# A7_MGT_-.net
KiCad netlist of a schematic drawn in Altium Designer
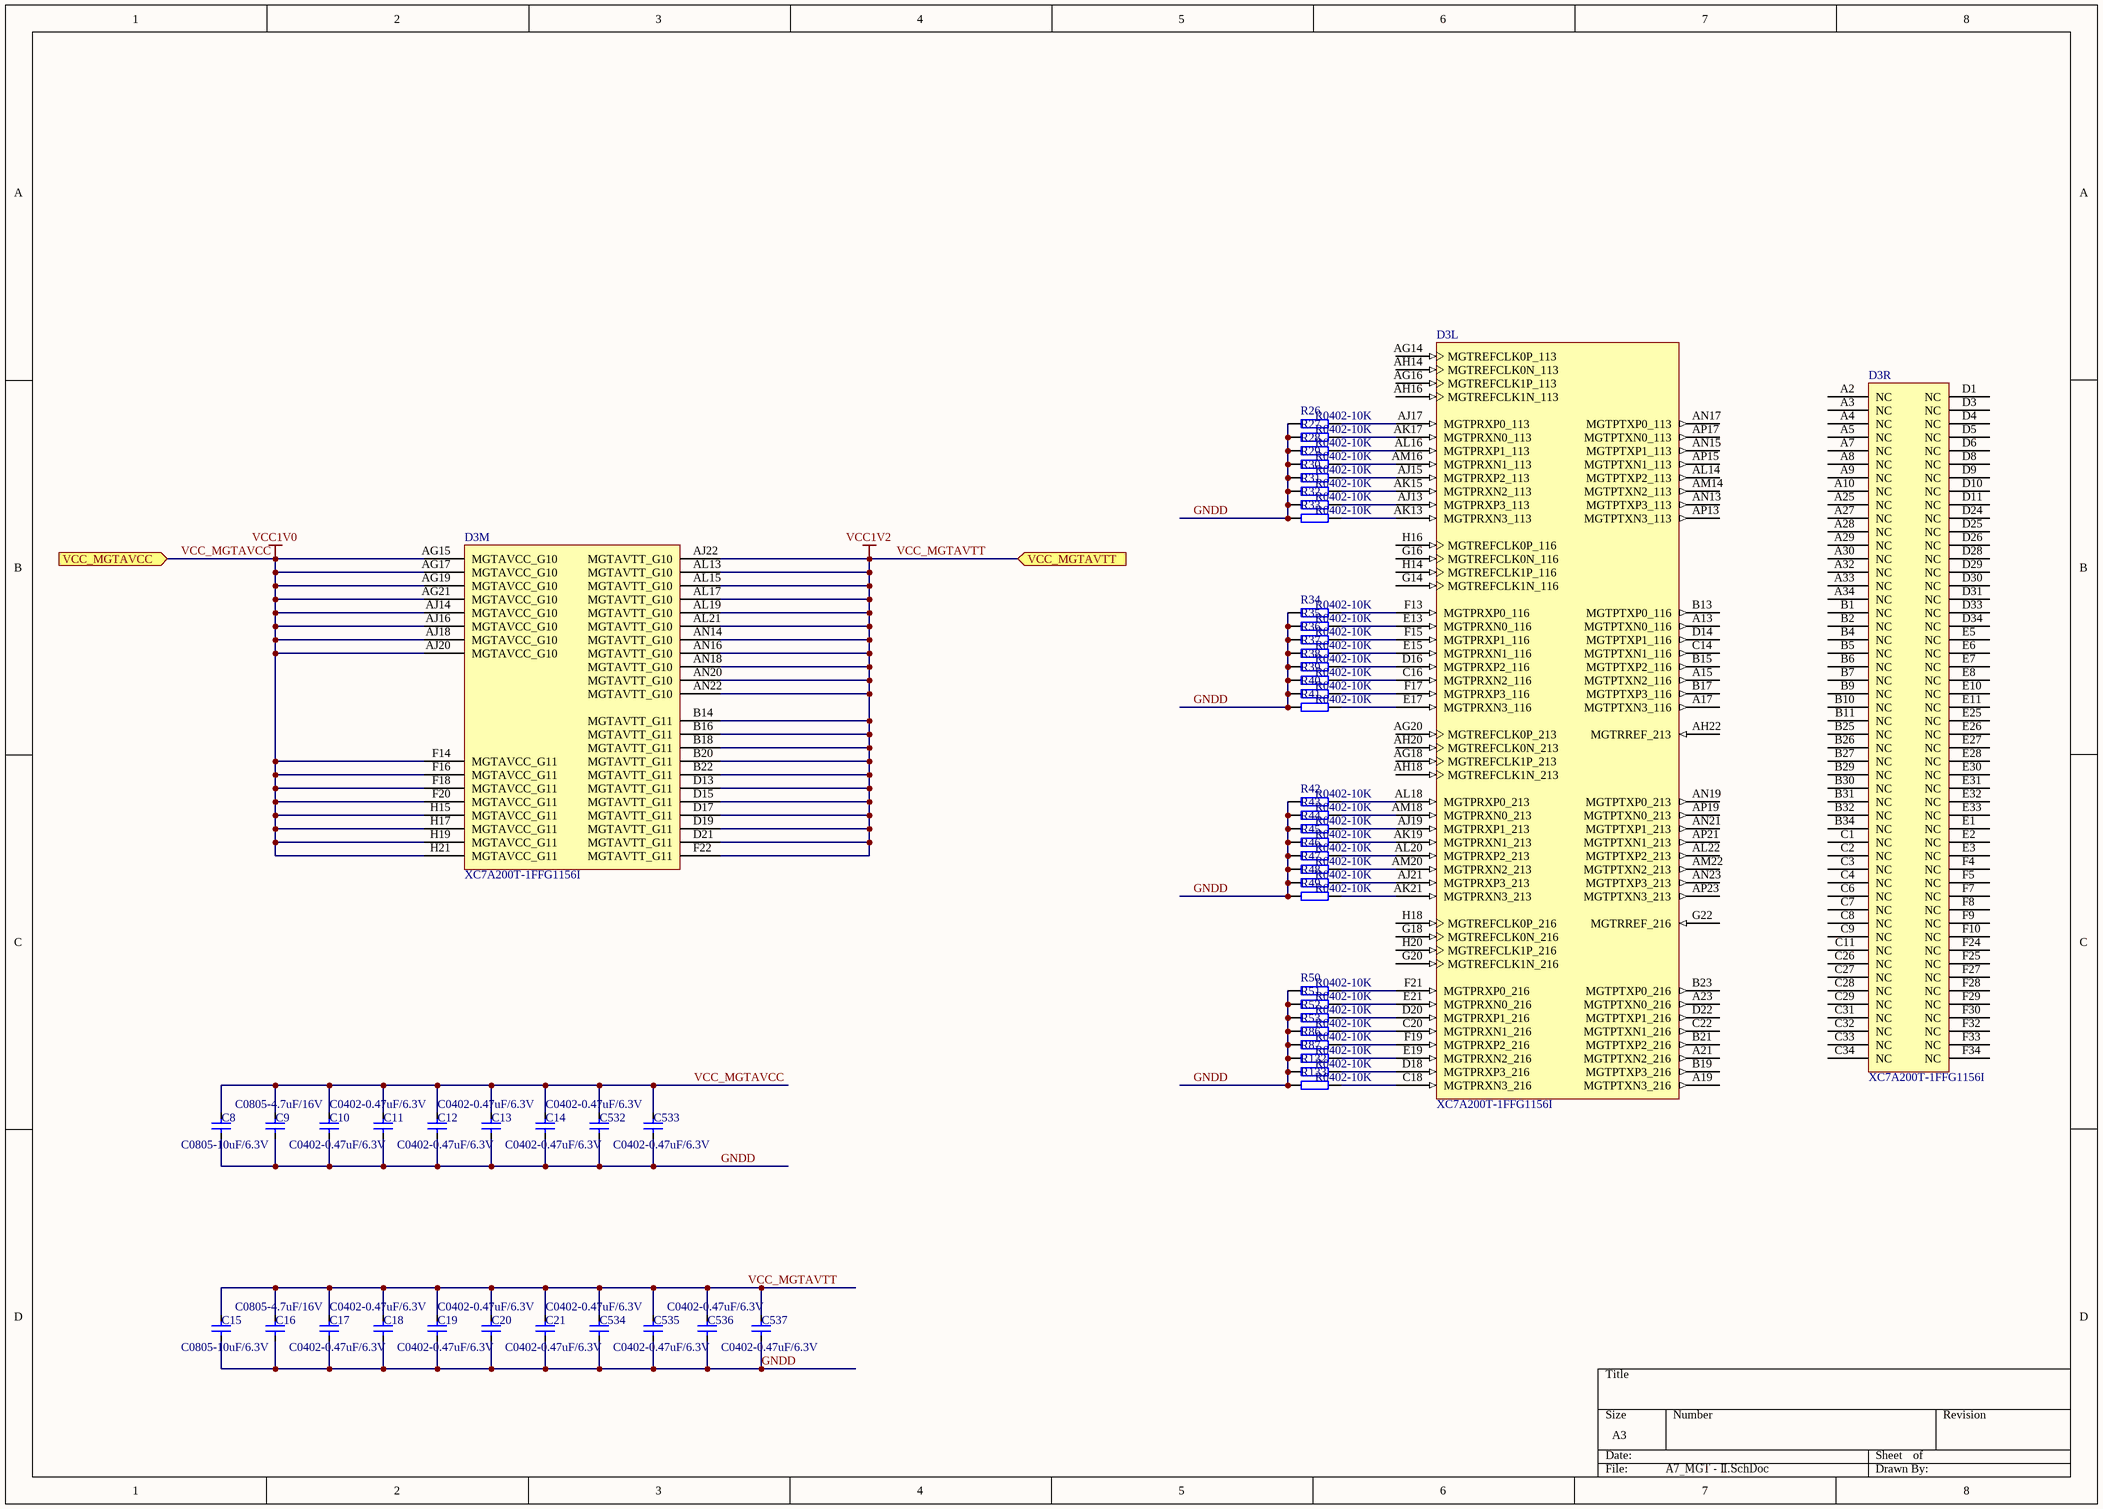
[diagram p0: A7_MGT - Ⅱ.SchDoc]

(export (version "E")
  (design (tool "Eeschema 10.0.6"))
  (components
    (comp (ref "C8")
      (value "C0805-10uF/6.3V")
      (footprint "C0805")
      (fields (field (name "SCHEMATIC_PART") "CAP"))
      (libsource (lib "Database_Libs1") (part "CAP"))
    )
    (comp (ref "C9")
      (value "C0805-4.7uF/16V")
      (footprint "C0805")
      (description "X7R")
      (fields (field (name "SCHEMATIC_PART") "CAP") (field (name "MANUFACTURER") "SAMSUNG"))
      (libsource (lib "Database_Libs1") (part "CAP"))
    )
    (comp (ref "C10")
      (value "C0402-0.47uF/6.3V")
      (footprint "C0402")
      (description "X7R")
      (fields (field (name "SCHEMATIC_PART") "CAP") (field (name "MANUFACTURER") "SAMSUNG"))
      (libsource (lib "Database_Libs1") (part "CAP"))
    )
    (comp (ref "C11")
      (value "C0402-0.47uF/6.3V")
      (footprint "C0402")
      (description "X7R")
      (fields (field (name "SCHEMATIC_PART") "CAP") (field (name "MANUFACTURER") "SAMSUNG"))
      (libsource (lib "Database_Libs1") (part "CAP"))
    )
    (comp (ref "C12")
      (value "C0402-0.47uF/6.3V")
      (footprint "C0402")
      (description "X7R")
      (fields (field (name "SCHEMATIC_PART") "CAP") (field (name "MANUFACTURER") "SAMSUNG"))
      (libsource (lib "Database_Libs1") (part "CAP"))
    )
    (comp (ref "C13")
      (value "C0402-0.47uF/6.3V")
      (footprint "C0402")
      (description "X7R")
      (fields (field (name "SCHEMATIC_PART") "CAP") (field (name "MANUFACTURER") "SAMSUNG"))
      (libsource (lib "Database_Libs1") (part "CAP"))
    )
    (comp (ref "C14")
      (value "C0402-0.47uF/6.3V")
      (footprint "C0402")
      (description "X7R")
      (fields (field (name "SCHEMATIC_PART") "CAP") (field (name "MANUFACTURER") "SAMSUNG"))
      (libsource (lib "Database_Libs1") (part "CAP"))
    )
    (comp (ref "C15")
      (value "C0805-10uF/6.3V")
      (footprint "C0805")
      (fields (field (name "SCHEMATIC_PART") "CAP"))
      (libsource (lib "Database_Libs1") (part "CAP"))
    )
    (comp (ref "C16")
      (value "C0805-4.7uF/16V")
      (footprint "C0805")
      (description "X7R")
      (fields (field (name "SCHEMATIC_PART") "CAP") (field (name "MANUFACTURER") "SAMSUNG"))
      (libsource (lib "Database_Libs1") (part "CAP"))
    )
    (comp (ref "C17")
      (value "C0402-0.47uF/6.3V")
      (footprint "C0402")
      (description "X7R")
      (fields (field (name "SCHEMATIC_PART") "CAP") (field (name "MANUFACTURER") "SAMSUNG"))
      (libsource (lib "Database_Libs1") (part "CAP"))
    )
    (comp (ref "C18")
      (value "C0402-0.47uF/6.3V")
      (footprint "C0402")
      (description "X7R")
      (fields (field (name "SCHEMATIC_PART") "CAP") (field (name "MANUFACTURER") "SAMSUNG"))
      (libsource (lib "Database_Libs1") (part "CAP"))
    )
    (comp (ref "C19")
      (value "C0402-0.47uF/6.3V")
      (footprint "C0402")
      (description "X7R")
      (fields (field (name "SCHEMATIC_PART") "CAP") (field (name "MANUFACTURER") "SAMSUNG"))
      (libsource (lib "Database_Libs1") (part "CAP"))
    )
    (comp (ref "C20")
      (value "C0402-0.47uF/6.3V")
      (footprint "C0402")
      (description "X7R")
      (fields (field (name "SCHEMATIC_PART") "CAP") (field (name "MANUFACTURER") "SAMSUNG"))
      (libsource (lib "Database_Libs1") (part "CAP"))
    )
    (comp (ref "C21")
      (value "C0402-0.47uF/6.3V")
      (footprint "C0402")
      (description "X7R")
      (fields (field (name "SCHEMATIC_PART") "CAP") (field (name "MANUFACTURER") "SAMSUNG"))
      (libsource (lib "Database_Libs1") (part "CAP"))
    )
    (comp (ref "C532")
      (value "C0402-0.47uF/6.3V")
      (footprint "C0402")
      (description "X7R")
      (fields (field (name "SCHEMATIC_PART") "CAP") (field (name "MANUFACTURER") "SAMSUNG"))
      (libsource (lib "Database_Libs1") (part "CAP"))
    )
    (comp (ref "C533")
      (value "C0402-0.47uF/6.3V")
      (footprint "C0402")
      (description "X7R")
      (fields (field (name "SCHEMATIC_PART") "CAP") (field (name "MANUFACTURER") "SAMSUNG"))
      (libsource (lib "Database_Libs1") (part "CAP"))
    )
    (comp (ref "C534")
      (value "C0402-0.47uF/6.3V")
      (footprint "C0402")
      (description "X7R")
      (fields (field (name "SCHEMATIC_PART") "CAP") (field (name "MANUFACTURER") "SAMSUNG"))
      (libsource (lib "Database_Libs1") (part "CAP"))
    )
    (comp (ref "C535")
      (value "C0402-0.47uF/6.3V")
      (footprint "C0402")
      (description "X7R")
      (fields (field (name "SCHEMATIC_PART") "CAP") (field (name "MANUFACTURER") "SAMSUNG"))
      (libsource (lib "Database_Libs1") (part "CAP"))
    )
    (comp (ref "C536")
      (value "C0402-0.47uF/6.3V")
      (footprint "C0402")
      (description "X7R")
      (fields (field (name "SCHEMATIC_PART") "CAP") (field (name "MANUFACTURER") "SAMSUNG"))
      (libsource (lib "Database_Libs1") (part "CAP"))
    )
    (comp (ref "C537")
      (value "C0402-0.47uF/6.3V")
      (footprint "C0402")
      (description "X7R")
      (fields (field (name "SCHEMATIC_PART") "CAP") (field (name "MANUFACTURER") "SAMSUNG"))
      (libsource (lib "Database_Libs1") (part "CAP"))
    )
    (comp (ref "D3")
      (value "XC7A200T-1FFG1156I")
      (footprint "FFG1156")
      (description "Artix-7 FPGA, 500 User I/Os, 16 GTP, 1156-Ball BGA, Speed Grade 1, Industrial Grade, Pb-Free")
      (fields (field (name "GENERIC PART NUMBER") "XC7A200T") (field (name "MANUFACTURER") "Xilinx"))
      (libsource (lib "Xilinx Artix-7") (part "XC7A200T-1FFG1156I"))
    )
    (comp (ref "R26")
      (value "R0402-10K")
      (footprint "R0402")
      (fields (field (name "SCHEMATIC_PART") "RES") (field (name "MANUFACTURER") "SAMSUNG"))
      (libsource (lib "Database_Libs1") (part "RES"))
    )
    (comp (ref "R27")
      (value "R0402-10K")
      (footprint "R0402")
      (fields (field (name "SCHEMATIC_PART") "RES") (field (name "MANUFACTURER") "SAMSUNG"))
      (libsource (lib "Database_Libs1") (part "RES"))
    )
    (comp (ref "R28")
      (value "R0402-10K")
      (footprint "R0402")
      (fields (field (name "SCHEMATIC_PART") "RES") (field (name "MANUFACTURER") "SAMSUNG"))
      (libsource (lib "Database_Libs1") (part "RES"))
    )
    (comp (ref "R29")
      (value "R0402-10K")
      (footprint "R0402")
      (fields (field (name "SCHEMATIC_PART") "RES") (field (name "MANUFACTURER") "SAMSUNG"))
      (libsource (lib "Database_Libs1") (part "RES"))
    )
    (comp (ref "R30")
      (value "R0402-10K")
      (footprint "R0402")
      (fields (field (name "SCHEMATIC_PART") "RES") (field (name "MANUFACTURER") "SAMSUNG"))
      (libsource (lib "Database_Libs1") (part "RES"))
    )
    (comp (ref "R31")
      (value "R0402-10K")
      (footprint "R0402")
      (fields (field (name "SCHEMATIC_PART") "RES") (field (name "MANUFACTURER") "SAMSUNG"))
      (libsource (lib "Database_Libs1") (part "RES"))
    )
    (comp (ref "R32")
      (value "R0402-10K")
      (footprint "R0402")
      (fields (field (name "SCHEMATIC_PART") "RES") (field (name "MANUFACTURER") "SAMSUNG"))
      (libsource (lib "Database_Libs1") (part "RES"))
    )
    (comp (ref "R33")
      (value "R0402-10K")
      (footprint "R0402")
      (fields (field (name "SCHEMATIC_PART") "RES") (field (name "MANUFACTURER") "SAMSUNG"))
      (libsource (lib "Database_Libs1") (part "RES"))
    )
    (comp (ref "R34")
      (value "R0402-10K")
      (footprint "R0402")
      (fields (field (name "SCHEMATIC_PART") "RES") (field (name "MANUFACTURER") "SAMSUNG"))
      (libsource (lib "Database_Libs1") (part "RES"))
    )
    (comp (ref "R35")
      (value "R0402-10K")
      (footprint "R0402")
      (fields (field (name "SCHEMATIC_PART") "RES") (field (name "MANUFACTURER") "SAMSUNG"))
      (libsource (lib "Database_Libs1") (part "RES"))
    )
    (comp (ref "R36")
      (value "R0402-10K")
      (footprint "R0402")
      (fields (field (name "SCHEMATIC_PART") "RES") (field (name "MANUFACTURER") "SAMSUNG"))
      (libsource (lib "Database_Libs1") (part "RES"))
    )
    (comp (ref "R37")
      (value "R0402-10K")
      (footprint "R0402")
      (fields (field (name "SCHEMATIC_PART") "RES") (field (name "MANUFACTURER") "SAMSUNG"))
      (libsource (lib "Database_Libs1") (part "RES"))
    )
    (comp (ref "R38")
      (value "R0402-10K")
      (footprint "R0402")
      (fields (field (name "SCHEMATIC_PART") "RES") (field (name "MANUFACTURER") "SAMSUNG"))
      (libsource (lib "Database_Libs1") (part "RES"))
    )
    (comp (ref "R39")
      (value "R0402-10K")
      (footprint "R0402")
      (fields (field (name "SCHEMATIC_PART") "RES") (field (name "MANUFACTURER") "SAMSUNG"))
      (libsource (lib "Database_Libs1") (part "RES"))
    )
    (comp (ref "R40")
      (value "R0402-10K")
      (footprint "R0402")
      (fields (field (name "SCHEMATIC_PART") "RES") (field (name "MANUFACTURER") "SAMSUNG"))
      (libsource (lib "Database_Libs1") (part "RES"))
    )
    (comp (ref "R41")
      (value "R0402-10K")
      (footprint "R0402")
      (fields (field (name "SCHEMATIC_PART") "RES") (field (name "MANUFACTURER") "SAMSUNG"))
      (libsource (lib "Database_Libs1") (part "RES"))
    )
    (comp (ref "R42")
      (value "R0402-10K")
      (footprint "R0402")
      (fields (field (name "SCHEMATIC_PART") "RES") (field (name "MANUFACTURER") "SAMSUNG"))
      (libsource (lib "Database_Libs1") (part "RES"))
    )
    (comp (ref "R43")
      (value "R0402-10K")
      (footprint "R0402")
      (fields (field (name "SCHEMATIC_PART") "RES") (field (name "MANUFACTURER") "SAMSUNG"))
      (libsource (lib "Database_Libs1") (part "RES"))
    )
    (comp (ref "R44")
      (value "R0402-10K")
      (footprint "R0402")
      (fields (field (name "SCHEMATIC_PART") "RES") (field (name "MANUFACTURER") "SAMSUNG"))
      (libsource (lib "Database_Libs1") (part "RES"))
    )
    (comp (ref "R45")
      (value "R0402-10K")
      (footprint "R0402")
      (fields (field (name "SCHEMATIC_PART") "RES") (field (name "MANUFACTURER") "SAMSUNG"))
      (libsource (lib "Database_Libs1") (part "RES"))
    )
    (comp (ref "R46")
      (value "R0402-10K")
      (footprint "R0402")
      (fields (field (name "SCHEMATIC_PART") "RES") (field (name "MANUFACTURER") "SAMSUNG"))
      (libsource (lib "Database_Libs1") (part "RES"))
    )
    (comp (ref "R47")
      (value "R0402-10K")
      (footprint "R0402")
      (fields (field (name "SCHEMATIC_PART") "RES") (field (name "MANUFACTURER") "SAMSUNG"))
      (libsource (lib "Database_Libs1") (part "RES"))
    )
    (comp (ref "R48")
      (value "R0402-10K")
      (footprint "R0402")
      (fields (field (name "SCHEMATIC_PART") "RES") (field (name "MANUFACTURER") "SAMSUNG"))
      (libsource (lib "Database_Libs1") (part "RES"))
    )
    (comp (ref "R49")
      (value "R0402-10K")
      (footprint "R0402")
      (fields (field (name "SCHEMATIC_PART") "RES") (field (name "MANUFACTURER") "SAMSUNG"))
      (libsource (lib "Database_Libs1") (part "RES"))
    )
    (comp (ref "R50")
      (value "R0402-10K")
      (footprint "R0402")
      (fields (field (name "SCHEMATIC_PART") "RES") (field (name "MANUFACTURER") "SAMSUNG"))
      (libsource (lib "Database_Libs1") (part "RES"))
    )
    (comp (ref "R51")
      (value "R0402-10K")
      (footprint "R0402")
      (fields (field (name "SCHEMATIC_PART") "RES") (field (name "MANUFACTURER") "SAMSUNG"))
      (libsource (lib "Database_Libs1") (part "RES"))
    )
    (comp (ref "R52")
      (value "R0402-10K")
      (footprint "R0402")
      (fields (field (name "SCHEMATIC_PART") "RES") (field (name "MANUFACTURER") "SAMSUNG"))
      (libsource (lib "Database_Libs1") (part "RES"))
    )
    (comp (ref "R53")
      (value "R0402-10K")
      (footprint "R0402")
      (fields (field (name "SCHEMATIC_PART") "RES") (field (name "MANUFACTURER") "SAMSUNG"))
      (libsource (lib "Database_Libs1") (part "RES"))
    )
    (comp (ref "R86")
      (value "R0402-10K")
      (footprint "R0402")
      (fields (field (name "SCHEMATIC_PART") "RES") (field (name "MANUFACTURER") "SAMSUNG"))
      (libsource (lib "Database_Libs1") (part "RES"))
    )
    (comp (ref "R87")
      (value "R0402-10K")
      (footprint "R0402")
      (fields (field (name "SCHEMATIC_PART") "RES") (field (name "MANUFACTURER") "SAMSUNG"))
      (libsource (lib "Database_Libs1") (part "RES"))
    )
    (comp (ref "R132")
      (value "R0402-10K")
      (footprint "R0402")
      (fields (field (name "SCHEMATIC_PART") "RES") (field (name "MANUFACTURER") "SAMSUNG"))
      (libsource (lib "Database_Libs1") (part "RES"))
    )
    (comp (ref "R133")
      (value "R0402-10K")
      (footprint "R0402")
      (fields (field (name "SCHEMATIC_PART") "RES") (field (name "MANUFACTURER") "SAMSUNG"))
      (libsource (lib "Database_Libs1") (part "RES"))
    )
  )
  (nets
    (net (code "1") (name "/GNDD") (class "Default")
      (node (ref "C10") (pin "2") (pinfunction "2_2") (pintype "passive"))
      (node (ref "C11") (pin "2") (pinfunction "2_2") (pintype "passive"))
      (node (ref "C12") (pin "2") (pinfunction "2_2") (pintype "passive"))
      (node (ref "C13") (pin "2") (pinfunction "2_2") (pintype "passive"))
      (node (ref "C14") (pin "2") (pinfunction "2_2") (pintype "passive"))
      (node (ref "C15") (pin "2") (pinfunction "2_2") (pintype "passive"))
      (node (ref "C16") (pin "2") (pinfunction "2_2") (pintype "passive"))
      (node (ref "C17") (pin "2") (pinfunction "2_2") (pintype "passive"))
      (node (ref "C18") (pin "2") (pinfunction "2_2") (pintype "passive"))
      (node (ref "C19") (pin "2") (pinfunction "2_2") (pintype "passive"))
      (node (ref "C20") (pin "2") (pinfunction "2_2") (pintype "passive"))
      (node (ref "C21") (pin "2") (pinfunction "2_2") (pintype "passive"))
      (node (ref "C532") (pin "2") (pinfunction "2_2") (pintype "passive"))
      (node (ref "C533") (pin "2") (pinfunction "2_2") (pintype "passive"))
      (node (ref "C534") (pin "2") (pinfunction "2_2") (pintype "passive"))
      (node (ref "C535") (pin "2") (pinfunction "2_2") (pintype "passive"))
      (node (ref "C536") (pin "2") (pinfunction "2_2") (pintype "passive"))
      (node (ref "C537") (pin "2") (pinfunction "2_2") (pintype "passive"))
      (node (ref "C8") (pin "2") (pinfunction "2_2") (pintype "passive"))
      (node (ref "C9") (pin "2") (pinfunction "2_2") (pintype "passive"))
      (node (ref "R132") (pin "1") (pintype "passive"))
      (node (ref "R133") (pin "1") (pintype "passive"))
      (node (ref "R26") (pin "1") (pintype "passive"))
      (node (ref "R27") (pin "1") (pintype "passive"))
      (node (ref "R28") (pin "1") (pintype "passive"))
      (node (ref "R29") (pin "1") (pintype "passive"))
      (node (ref "R30") (pin "1") (pintype "passive"))
      (node (ref "R31") (pin "1") (pintype "passive"))
      (node (ref "R32") (pin "1") (pintype "passive"))
      (node (ref "R33") (pin "1") (pintype "passive"))
      (node (ref "R34") (pin "1") (pintype "passive"))
      (node (ref "R35") (pin "1") (pintype "passive"))
      (node (ref "R36") (pin "1") (pintype "passive"))
      (node (ref "R37") (pin "1") (pintype "passive"))
      (node (ref "R38") (pin "1") (pintype "passive"))
      (node (ref "R39") (pin "1") (pintype "passive"))
      (node (ref "R40") (pin "1") (pintype "passive"))
      (node (ref "R41") (pin "1") (pintype "passive"))
      (node (ref "R42") (pin "1") (pintype "passive"))
      (node (ref "R43") (pin "1") (pintype "passive"))
      (node (ref "R44") (pin "1") (pintype "passive"))
      (node (ref "R45") (pin "1") (pintype "passive"))
      (node (ref "R46") (pin "1") (pintype "passive"))
      (node (ref "R47") (pin "1") (pintype "passive"))
      (node (ref "R48") (pin "1") (pintype "passive"))
      (node (ref "R49") (pin "1") (pintype "passive"))
      (node (ref "R50") (pin "1") (pintype "passive"))
      (node (ref "R51") (pin "1") (pintype "passive"))
      (node (ref "R52") (pin "1") (pintype "passive"))
      (node (ref "R53") (pin "1") (pintype "passive"))
      (node (ref "R86") (pin "1") (pintype "passive"))
      (node (ref "R87") (pin "1") (pintype "passive"))
    )
    (net (code "2") (name "Net-(D3L-MGTPRXN0_113)") (class "Default")
      (node (ref "D3") (pin "AK17") (pinfunction "MGTPRXN0_113_AK17") (pintype "input"))
      (node (ref "R27") (pin "2") (pintype "passive"))
    )
    (net (code "3") (name "Net-(D3L-MGTPRXN0_116)") (class "Default")
      (node (ref "D3") (pin "E13") (pinfunction "MGTPRXN0_116_E13") (pintype "input"))
      (node (ref "R35") (pin "2") (pintype "passive"))
    )
    (net (code "4") (name "Net-(D3L-MGTPRXN0_213)") (class "Default")
      (node (ref "D3") (pin "AM18") (pinfunction "MGTPRXN0_213_AM18") (pintype "input"))
      (node (ref "R43") (pin "2") (pintype "passive"))
    )
    (net (code "5") (name "Net-(D3L-MGTPRXN0_216)") (class "Default")
      (node (ref "D3") (pin "E21") (pinfunction "MGTPRXN0_216_E21") (pintype "input"))
      (node (ref "R51") (pin "2") (pintype "passive"))
    )
    (net (code "6") (name "Net-(D3L-MGTPRXN1_113)") (class "Default")
      (node (ref "D3") (pin "AM16") (pinfunction "MGTPRXN1_113_AM16") (pintype "input"))
      (node (ref "R29") (pin "2") (pintype "passive"))
    )
    (net (code "7") (name "Net-(D3L-MGTPRXN1_116)") (class "Default")
      (node (ref "D3") (pin "E15") (pinfunction "MGTPRXN1_116_E15") (pintype "input"))
      (node (ref "R37") (pin "2") (pintype "passive"))
    )
    (net (code "8") (name "Net-(D3L-MGTPRXN1_213)") (class "Default")
      (node (ref "D3") (pin "AK19") (pinfunction "MGTPRXN1_213_AK19") (pintype "input"))
      (node (ref "R45") (pin "2") (pintype "passive"))
    )
    (net (code "9") (name "Net-(D3L-MGTPRXN1_216)") (class "Default")
      (node (ref "D3") (pin "C20") (pinfunction "MGTPRXN1_216_C20") (pintype "input"))
      (node (ref "R53") (pin "2") (pintype "passive"))
    )
    (net (code "10") (name "Net-(D3L-MGTPRXN2_113)") (class "Default")
      (node (ref "D3") (pin "AK15") (pinfunction "MGTPRXN2_113_AK15") (pintype "input"))
      (node (ref "R31") (pin "2") (pintype "passive"))
    )
    (net (code "11") (name "Net-(D3L-MGTPRXN2_116)") (class "Default")
      (node (ref "D3") (pin "C16") (pinfunction "MGTPRXN2_116_C16") (pintype "input"))
      (node (ref "R39") (pin "2") (pintype "passive"))
    )
    (net (code "12") (name "Net-(D3L-MGTPRXN2_213)") (class "Default")
      (node (ref "D3") (pin "AM20") (pinfunction "MGTPRXN2_213_AM20") (pintype "input"))
      (node (ref "R47") (pin "2") (pintype "passive"))
    )
    (net (code "13") (name "Net-(D3L-MGTPRXN2_216)") (class "Default")
      (node (ref "D3") (pin "E19") (pinfunction "MGTPRXN2_216_E19") (pintype "input"))
      (node (ref "R87") (pin "2") (pintype "passive"))
    )
    (net (code "14") (name "Net-(D3L-MGTPRXN3_113)") (class "Default")
      (node (ref "D3") (pin "AK13") (pinfunction "MGTPRXN3_113_AK13") (pintype "input"))
      (node (ref "R33") (pin "2") (pintype "passive"))
    )
    (net (code "15") (name "Net-(D3L-MGTPRXN3_116)") (class "Default")
      (node (ref "D3") (pin "E17") (pinfunction "MGTPRXN3_116_E17") (pintype "input"))
      (node (ref "R41") (pin "2") (pintype "passive"))
    )
    (net (code "16") (name "Net-(D3L-MGTPRXN3_213)") (class "Default")
      (node (ref "D3") (pin "AK21") (pinfunction "MGTPRXN3_213_AK21") (pintype "input"))
      (node (ref "R49") (pin "2") (pintype "passive"))
    )
    (net (code "17") (name "Net-(D3L-MGTPRXN3_216)") (class "Default")
      (node (ref "D3") (pin "C18") (pinfunction "MGTPRXN3_216_C18") (pintype "input"))
      (node (ref "R133") (pin "2") (pintype "passive"))
    )
    (net (code "18") (name "Net-(D3L-MGTPRXP0_113)") (class "Default")
      (node (ref "D3") (pin "AJ17") (pinfunction "MGTPRXP0_113_AJ17") (pintype "input"))
      (node (ref "R26") (pin "2") (pintype "passive"))
    )
    (net (code "19") (name "Net-(D3L-MGTPRXP0_116)") (class "Default")
      (node (ref "D3") (pin "F13") (pinfunction "MGTPRXP0_116_F13") (pintype "input"))
      (node (ref "R34") (pin "2") (pintype "passive"))
    )
    (net (code "20") (name "Net-(D3L-MGTPRXP0_213)") (class "Default")
      (node (ref "D3") (pin "AL18") (pinfunction "MGTPRXP0_213_AL18") (pintype "input"))
      (node (ref "R42") (pin "2") (pintype "passive"))
    )
    (net (code "21") (name "Net-(D3L-MGTPRXP0_216)") (class "Default")
      (node (ref "D3") (pin "F21") (pinfunction "MGTPRXP0_216_F21") (pintype "input"))
      (node (ref "R50") (pin "2") (pintype "passive"))
    )
    (net (code "22") (name "Net-(D3L-MGTPRXP1_113)") (class "Default")
      (node (ref "D3") (pin "AL16") (pinfunction "MGTPRXP1_113_AL16") (pintype "input"))
      (node (ref "R28") (pin "2") (pintype "passive"))
    )
    (net (code "23") (name "Net-(D3L-MGTPRXP1_116)") (class "Default")
      (node (ref "D3") (pin "F15") (pinfunction "MGTPRXP1_116_F15") (pintype "input"))
      (node (ref "R36") (pin "2") (pintype "passive"))
    )
    (net (code "24") (name "Net-(D3L-MGTPRXP1_213)") (class "Default")
      (node (ref "D3") (pin "AJ19") (pinfunction "MGTPRXP1_213_AJ19") (pintype "input"))
      (node (ref "R44") (pin "2") (pintype "passive"))
    )
    (net (code "25") (name "Net-(D3L-MGTPRXP1_216)") (class "Default")
      (node (ref "D3") (pin "D20") (pinfunction "MGTPRXP1_216_D20") (pintype "input"))
      (node (ref "R52") (pin "2") (pintype "passive"))
    )
    (net (code "26") (name "Net-(D3L-MGTPRXP2_113)") (class "Default")
      (node (ref "D3") (pin "AJ15") (pinfunction "MGTPRXP2_113_AJ15") (pintype "input"))
      (node (ref "R30") (pin "2") (pintype "passive"))
    )
    (net (code "27") (name "Net-(D3L-MGTPRXP2_116)") (class "Default")
      (node (ref "D3") (pin "D16") (pinfunction "MGTPRXP2_116_D16") (pintype "input"))
      (node (ref "R38") (pin "2") (pintype "passive"))
    )
    (net (code "28") (name "Net-(D3L-MGTPRXP2_213)") (class "Default")
      (node (ref "D3") (pin "AL20") (pinfunction "MGTPRXP2_213_AL20") (pintype "input"))
      (node (ref "R46") (pin "2") (pintype "passive"))
    )
    (net (code "29") (name "Net-(D3L-MGTPRXP2_216)") (class "Default")
      (node (ref "D3") (pin "F19") (pinfunction "MGTPRXP2_216_F19") (pintype "input"))
      (node (ref "R86") (pin "2") (pintype "passive"))
    )
    (net (code "30") (name "Net-(D3L-MGTPRXP3_113)") (class "Default")
      (node (ref "D3") (pin "AJ13") (pinfunction "MGTPRXP3_113_AJ13") (pintype "input"))
      (node (ref "R32") (pin "2") (pintype "passive"))
    )
    (net (code "31") (name "Net-(D3L-MGTPRXP3_116)") (class "Default")
      (node (ref "D3") (pin "F17") (pinfunction "MGTPRXP3_116_F17") (pintype "input"))
      (node (ref "R40") (pin "2") (pintype "passive"))
    )
    (net (code "32") (name "Net-(D3L-MGTPRXP3_213)") (class "Default")
      (node (ref "D3") (pin "AJ21") (pinfunction "MGTPRXP3_213_AJ21") (pintype "input"))
      (node (ref "R48") (pin "2") (pintype "passive"))
    )
    (net (code "33") (name "Net-(D3L-MGTPRXP3_216)") (class "Default")
      (node (ref "D3") (pin "D18") (pinfunction "MGTPRXP3_216_D18") (pintype "input"))
      (node (ref "R132") (pin "2") (pintype "passive"))
    )
    (net (code "34") (name "VCC1V0") (class "Default")
      (node (ref "C10") (pin "1") (pinfunction "1_1") (pintype "passive"))
      (node (ref "C11") (pin "1") (pinfunction "1_1") (pintype "passive"))
      (node (ref "C12") (pin "1") (pinfunction "1_1") (pintype "passive"))
      (node (ref "C13") (pin "1") (pinfunction "1_1") (pintype "passive"))
      (node (ref "C14") (pin "1") (pinfunction "1_1") (pintype "passive"))
      (node (ref "C532") (pin "1") (pinfunction "1_1") (pintype "passive"))
      (node (ref "C533") (pin "1") (pinfunction "1_1") (pintype "passive"))
      (node (ref "C8") (pin "1") (pinfunction "1_1") (pintype "passive"))
      (node (ref "C9") (pin "1") (pinfunction "1_1") (pintype "passive"))
      (node (ref "D3") (pin "AG15") (pinfunction "MGTAVCC_G10_AG15") (pintype "power_in"))
      (node (ref "D3") (pin "AG17") (pinfunction "MGTAVCC_G10_AG17") (pintype "power_in"))
      (node (ref "D3") (pin "AG19") (pinfunction "MGTAVCC_G10_AG19") (pintype "power_in"))
      (node (ref "D3") (pin "AG21") (pinfunction "MGTAVCC_G10_AG21") (pintype "power_in"))
      (node (ref "D3") (pin "AJ14") (pinfunction "MGTAVCC_G10_AJ14") (pintype "power_in"))
      (node (ref "D3") (pin "AJ16") (pinfunction "MGTAVCC_G10_AJ16") (pintype "power_in"))
      (node (ref "D3") (pin "AJ18") (pinfunction "MGTAVCC_G10_AJ18") (pintype "power_in"))
      (node (ref "D3") (pin "AJ20") (pinfunction "MGTAVCC_G10_AJ20") (pintype "power_in"))
      (node (ref "D3") (pin "F14") (pinfunction "MGTAVCC_G11_F14") (pintype "power_in"))
      (node (ref "D3") (pin "F16") (pinfunction "MGTAVCC_G11_F16") (pintype "power_in"))
      (node (ref "D3") (pin "F18") (pinfunction "MGTAVCC_G11_F18") (pintype "power_in"))
      (node (ref "D3") (pin "F20") (pinfunction "MGTAVCC_G11_F20") (pintype "power_in"))
      (node (ref "D3") (pin "H15") (pinfunction "MGTAVCC_G11_H15") (pintype "power_in"))
      (node (ref "D3") (pin "H17") (pinfunction "MGTAVCC_G11_H17") (pintype "power_in"))
      (node (ref "D3") (pin "H19") (pinfunction "MGTAVCC_G11_H19") (pintype "power_in"))
      (node (ref "D3") (pin "H21") (pinfunction "MGTAVCC_G11_H21") (pintype "power_in"))
    )
    (net (code "35") (name "VCC1V2") (class "Default")
      (node (ref "C15") (pin "1") (pinfunction "1_1") (pintype "passive"))
      (node (ref "C16") (pin "1") (pinfunction "1_1") (pintype "passive"))
      (node (ref "C17") (pin "1") (pinfunction "1_1") (pintype "passive"))
      (node (ref "C18") (pin "1") (pinfunction "1_1") (pintype "passive"))
      (node (ref "C19") (pin "1") (pinfunction "1_1") (pintype "passive"))
      (node (ref "C20") (pin "1") (pinfunction "1_1") (pintype "passive"))
      (node (ref "C21") (pin "1") (pinfunction "1_1") (pintype "passive"))
      (node (ref "C534") (pin "1") (pinfunction "1_1") (pintype "passive"))
      (node (ref "C535") (pin "1") (pinfunction "1_1") (pintype "passive"))
      (node (ref "C536") (pin "1") (pinfunction "1_1") (pintype "passive"))
      (node (ref "C537") (pin "1") (pinfunction "1_1") (pintype "passive"))
      (node (ref "D3") (pin "AJ22") (pinfunction "MGTAVTT_G10_AJ22") (pintype "power_in"))
      (node (ref "D3") (pin "AL13") (pinfunction "MGTAVTT_G10_AL13") (pintype "power_in"))
      (node (ref "D3") (pin "AL15") (pinfunction "MGTAVTT_G10_AL15") (pintype "power_in"))
      (node (ref "D3") (pin "AL17") (pinfunction "MGTAVTT_G10_AL17") (pintype "power_in"))
      (node (ref "D3") (pin "AL19") (pinfunction "MGTAVTT_G10_AL19") (pintype "power_in"))
      (node (ref "D3") (pin "AL21") (pinfunction "MGTAVTT_G10_AL21") (pintype "power_in"))
      (node (ref "D3") (pin "AN14") (pinfunction "MGTAVTT_G10_AN14") (pintype "power_in"))
      (node (ref "D3") (pin "AN16") (pinfunction "MGTAVTT_G10_AN16") (pintype "power_in"))
      (node (ref "D3") (pin "AN18") (pinfunction "MGTAVTT_G10_AN18") (pintype "power_in"))
      (node (ref "D3") (pin "AN20") (pinfunction "MGTAVTT_G10_AN20") (pintype "power_in"))
      (node (ref "D3") (pin "AN22") (pinfunction "MGTAVTT_G10_AN22") (pintype "power_in"))
      (node (ref "D3") (pin "B14") (pinfunction "MGTAVTT_G11_B14") (pintype "power_in"))
      (node (ref "D3") (pin "B16") (pinfunction "MGTAVTT_G11_B16") (pintype "power_in"))
      (node (ref "D3") (pin "B18") (pinfunction "MGTAVTT_G11_B18") (pintype "power_in"))
      (node (ref "D3") (pin "B20") (pinfunction "MGTAVTT_G11_B20") (pintype "power_in"))
      (node (ref "D3") (pin "B22") (pinfunction "MGTAVTT_G11_B22") (pintype "power_in"))
      (node (ref "D3") (pin "D13") (pinfunction "MGTAVTT_G11_D13") (pintype "power_in"))
      (node (ref "D3") (pin "D15") (pinfunction "MGTAVTT_G11_D15") (pintype "power_in"))
      (node (ref "D3") (pin "D17") (pinfunction "MGTAVTT_G11_D17") (pintype "power_in"))
      (node (ref "D3") (pin "D19") (pinfunction "MGTAVTT_G11_D19") (pintype "power_in"))
      (node (ref "D3") (pin "D21") (pinfunction "MGTAVTT_G11_D21") (pintype "power_in"))
      (node (ref "D3") (pin "F22") (pinfunction "MGTAVTT_G11_F22") (pintype "power_in"))
    )
    (net (code "36") (name "unconnected-(D3L-MGTPTXN0_113-PadAP17)") (class "Default")
      (node (ref "D3") (pin "AP17") (pinfunction "MGTPTXN0_113_AP17") (pintype "output"))
    )
    (net (code "37") (name "unconnected-(D3L-MGTPTXN0_116-PadA13)") (class "Default")
      (node (ref "D3") (pin "A13") (pinfunction "MGTPTXN0_116_A13") (pintype "output"))
    )
    (net (code "38") (name "unconnected-(D3L-MGTPTXN0_213-PadAP19)") (class "Default")
      (node (ref "D3") (pin "AP19") (pinfunction "MGTPTXN0_213_AP19") (pintype "output"))
    )
    (net (code "39") (name "unconnected-(D3L-MGTPTXN0_216-PadA23)") (class "Default")
      (node (ref "D3") (pin "A23") (pinfunction "MGTPTXN0_216_A23") (pintype "output"))
    )
    (net (code "40") (name "unconnected-(D3L-MGTPTXN1_113-PadAP15)") (class "Default")
      (node (ref "D3") (pin "AP15") (pinfunction "MGTPTXN1_113_AP15") (pintype "output"))
    )
    (net (code "41") (name "unconnected-(D3L-MGTPTXN1_116-PadC14)") (class "Default")
      (node (ref "D3") (pin "C14") (pinfunction "MGTPTXN1_116_C14") (pintype "output"))
    )
    (net (code "42") (name "unconnected-(D3L-MGTPTXN1_213-PadAP21)") (class "Default")
      (node (ref "D3") (pin "AP21") (pinfunction "MGTPTXN1_213_AP21") (pintype "output"))
    )
    (net (code "43") (name "unconnected-(D3L-MGTPTXN1_216-PadC22)") (class "Default")
      (node (ref "D3") (pin "C22") (pinfunction "MGTPTXN1_216_C22") (pintype "output"))
    )
    (net (code "44") (name "unconnected-(D3L-MGTPTXN2_113-PadAM14)") (class "Default")
      (node (ref "D3") (pin "AM14") (pinfunction "MGTPTXN2_113_AM14") (pintype "output"))
    )
    (net (code "45") (name "unconnected-(D3L-MGTPTXN2_116-PadA15)") (class "Default")
      (node (ref "D3") (pin "A15") (pinfunction "MGTPTXN2_116_A15") (pintype "output"))
    )
    (net (code "46") (name "unconnected-(D3L-MGTPTXN2_213-PadAM22)") (class "Default")
      (node (ref "D3") (pin "AM22") (pinfunction "MGTPTXN2_213_AM22") (pintype "output"))
    )
    (net (code "47") (name "unconnected-(D3L-MGTPTXN2_216-PadA21)") (class "Default")
      (node (ref "D3") (pin "A21") (pinfunction "MGTPTXN2_216_A21") (pintype "output"))
    )
    (net (code "48") (name "unconnected-(D3L-MGTPTXN3_113-PadAP13)") (class "Default")
      (node (ref "D3") (pin "AP13") (pinfunction "MGTPTXN3_113_AP13") (pintype "output"))
    )
    (net (code "49") (name "unconnected-(D3L-MGTPTXN3_116-PadA17)") (class "Default")
      (node (ref "D3") (pin "A17") (pinfunction "MGTPTXN3_116_A17") (pintype "output"))
    )
    (net (code "50") (name "unconnected-(D3L-MGTPTXN3_213-PadAP23)") (class "Default")
      (node (ref "D3") (pin "AP23") (pinfunction "MGTPTXN3_213_AP23") (pintype "output"))
    )
    (net (code "51") (name "unconnected-(D3L-MGTPTXN3_216-PadA19)") (class "Default")
      (node (ref "D3") (pin "A19") (pinfunction "MGTPTXN3_216_A19") (pintype "output"))
    )
    (net (code "52") (name "unconnected-(D3L-MGTPTXP0_113-PadAN17)") (class "Default")
      (node (ref "D3") (pin "AN17") (pinfunction "MGTPTXP0_113_AN17") (pintype "output"))
    )
    (net (code "53") (name "unconnected-(D3L-MGTPTXP0_116-PadB13)") (class "Default")
      (node (ref "D3") (pin "B13") (pinfunction "MGTPTXP0_116_B13") (pintype "output"))
    )
    (net (code "54") (name "unconnected-(D3L-MGTPTXP0_213-PadAN19)") (class "Default")
      (node (ref "D3") (pin "AN19") (pinfunction "MGTPTXP0_213_AN19") (pintype "output"))
    )
    (net (code "55") (name "unconnected-(D3L-MGTPTXP0_216-PadB23)") (class "Default")
      (node (ref "D3") (pin "B23") (pinfunction "MGTPTXP0_216_B23") (pintype "output"))
    )
    (net (code "56") (name "unconnected-(D3L-MGTPTXP1_113-PadAN15)") (class "Default")
      (node (ref "D3") (pin "AN15") (pinfunction "MGTPTXP1_113_AN15") (pintype "output"))
    )
    (net (code "57") (name "unconnected-(D3L-MGTPTXP1_116-PadD14)") (class "Default")
      (node (ref "D3") (pin "D14") (pinfunction "MGTPTXP1_116_D14") (pintype "output"))
    )
    (net (code "58") (name "unconnected-(D3L-MGTPTXP1_213-PadAN21)") (class "Default")
      (node (ref "D3") (pin "AN21") (pinfunction "MGTPTXP1_213_AN21") (pintype "output"))
    )
    (net (code "59") (name "unconnected-(D3L-MGTPTXP1_216-PadD22)") (class "Default")
      (node (ref "D3") (pin "D22") (pinfunction "MGTPTXP1_216_D22") (pintype "output"))
    )
    (net (code "60") (name "unconnected-(D3L-MGTPTXP2_113-PadAL14)") (class "Default")
      (node (ref "D3") (pin "AL14") (pinfunction "MGTPTXP2_113_AL14") (pintype "output"))
    )
    (net (code "61") (name "unconnected-(D3L-MGTPTXP2_116-PadB15)") (class "Default")
      (node (ref "D3") (pin "B15") (pinfunction "MGTPTXP2_116_B15") (pintype "output"))
    )
    (net (code "62") (name "unconnected-(D3L-MGTPTXP2_213-PadAL22)") (class "Default")
      (node (ref "D3") (pin "AL22") (pinfunction "MGTPTXP2_213_AL22") (pintype "output"))
    )
    (net (code "63") (name "unconnected-(D3L-MGTPTXP2_216-PadB21)") (class "Default")
      (node (ref "D3") (pin "B21") (pinfunction "MGTPTXP2_216_B21") (pintype "output"))
    )
    (net (code "64") (name "unconnected-(D3L-MGTPTXP3_113-PadAN13)") (class "Default")
      (node (ref "D3") (pin "AN13") (pinfunction "MGTPTXP3_113_AN13") (pintype "output"))
    )
    (net (code "65") (name "unconnected-(D3L-MGTPTXP3_116-PadB17)") (class "Default")
      (node (ref "D3") (pin "B17") (pinfunction "MGTPTXP3_116_B17") (pintype "output"))
    )
    (net (code "66") (name "unconnected-(D3L-MGTPTXP3_213-PadAN23)") (class "Default")
      (node (ref "D3") (pin "AN23") (pinfunction "MGTPTXP3_213_AN23") (pintype "output"))
    )
    (net (code "67") (name "unconnected-(D3L-MGTPTXP3_216-PadB19)") (class "Default")
      (node (ref "D3") (pin "B19") (pinfunction "MGTPTXP3_216_B19") (pintype "output"))
    )
    (net (code "68") (name "unconnected-(D3L-MGTREFCLK0N_113-PadAH14)") (class "Default")
      (node (ref "D3") (pin "AH14") (pinfunction "MGTREFCLK0N_113_AH14") (pintype "input"))
    )
    (net (code "69") (name "unconnected-(D3L-MGTREFCLK0N_116-PadG16)") (class "Default")
      (node (ref "D3") (pin "G16") (pinfunction "MGTREFCLK0N_116_G16") (pintype "input"))
    )
    (net (code "70") (name "unconnected-(D3L-MGTREFCLK0N_213-PadAH20)") (class "Default")
      (node (ref "D3") (pin "AH20") (pinfunction "MGTREFCLK0N_213_AH20") (pintype "input"))
    )
    (net (code "71") (name "unconnected-(D3L-MGTREFCLK0N_216-PadG18)") (class "Default")
      (node (ref "D3") (pin "G18") (pinfunction "MGTREFCLK0N_216_G18") (pintype "input"))
    )
    (net (code "72") (name "unconnected-(D3L-MGTREFCLK0P_113-PadAG14)") (class "Default")
      (node (ref "D3") (pin "AG14") (pinfunction "MGTREFCLK0P_113_AG14") (pintype "input"))
    )
    (net (code "73") (name "unconnected-(D3L-MGTREFCLK0P_116-PadH16)") (class "Default")
      (node (ref "D3") (pin "H16") (pinfunction "MGTREFCLK0P_116_H16") (pintype "input"))
    )
    (net (code "74") (name "unconnected-(D3L-MGTREFCLK0P_213-PadAG20)") (class "Default")
      (node (ref "D3") (pin "AG20") (pinfunction "MGTREFCLK0P_213_AG20") (pintype "input"))
    )
    (net (code "75") (name "unconnected-(D3L-MGTREFCLK0P_216-PadH18)") (class "Default")
      (node (ref "D3") (pin "H18") (pinfunction "MGTREFCLK0P_216_H18") (pintype "input"))
    )
    (net (code "76") (name "unconnected-(D3L-MGTREFCLK1N_113-PadAH16)") (class "Default")
      (node (ref "D3") (pin "AH16") (pinfunction "MGTREFCLK1N_113_AH16") (pintype "input"))
    )
    (net (code "77") (name "unconnected-(D3L-MGTREFCLK1N_116-PadG14)") (class "Default")
      (node (ref "D3") (pin "G14") (pinfunction "MGTREFCLK1N_116_G14") (pintype "input"))
    )
    (net (code "78") (name "unconnected-(D3L-MGTREFCLK1N_213-PadAH18)") (class "Default")
      (node (ref "D3") (pin "AH18") (pinfunction "MGTREFCLK1N_213_AH18") (pintype "input"))
    )
    (net (code "79") (name "unconnected-(D3L-MGTREFCLK1N_216-PadG20)") (class "Default")
      (node (ref "D3") (pin "G20") (pinfunction "MGTREFCLK1N_216_G20") (pintype "input"))
    )
    (net (code "80") (name "unconnected-(D3L-MGTREFCLK1P_113-PadAG16)") (class "Default")
      (node (ref "D3") (pin "AG16") (pinfunction "MGTREFCLK1P_113_AG16") (pintype "input"))
    )
    (net (code "81") (name "unconnected-(D3L-MGTREFCLK1P_116-PadH14)") (class "Default")
      (node (ref "D3") (pin "H14") (pinfunction "MGTREFCLK1P_116_H14") (pintype "input"))
    )
    (net (code "82") (name "unconnected-(D3L-MGTREFCLK1P_213-PadAG18)") (class "Default")
      (node (ref "D3") (pin "AG18") (pinfunction "MGTREFCLK1P_213_AG18") (pintype "input"))
    )
    (net (code "83") (name "unconnected-(D3L-MGTREFCLK1P_216-PadH20)") (class "Default")
      (node (ref "D3") (pin "H20") (pinfunction "MGTREFCLK1P_216_H20") (pintype "input"))
    )
    (net (code "84") (name "unconnected-(D3L-MGTRREF_213-PadAH22)") (class "Default")
      (node (ref "D3") (pin "AH22") (pinfunction "MGTRREF_213_AH22") (pintype "input"))
    )
    (net (code "85") (name "unconnected-(D3L-MGTRREF_216-PadG22)") (class "Default")
      (node (ref "D3") (pin "G22") (pinfunction "MGTRREF_216_G22") (pintype "input"))
    )
    (net (code "86") (name "unconnected-(D3R-NC-PadA2)") (class "Default")
      (node (ref "D3") (pin "A2") (pinfunction "NC_A2") (pintype "passive"))
    )
    (net (code "87") (name "unconnected-(D3R-NC-PadA3)") (class "Default")
      (node (ref "D3") (pin "A3") (pinfunction "NC_A3") (pintype "passive"))
    )
    (net (code "88") (name "unconnected-(D3R-NC-PadA4)") (class "Default")
      (node (ref "D3") (pin "A4") (pinfunction "NC_A4") (pintype "passive"))
    )
    (net (code "89") (name "unconnected-(D3R-NC-PadA5)") (class "Default")
      (node (ref "D3") (pin "A5") (pinfunction "NC_A5") (pintype "passive"))
    )
    (net (code "90") (name "unconnected-(D3R-NC-PadA7)") (class "Default")
      (node (ref "D3") (pin "A7") (pinfunction "NC_A7") (pintype "passive"))
    )
    (net (code "91") (name "unconnected-(D3R-NC-PadA8)") (class "Default")
      (node (ref "D3") (pin "A8") (pinfunction "NC_A8") (pintype "passive"))
    )
    (net (code "92") (name "unconnected-(D3R-NC-PadA9)") (class "Default")
      (node (ref "D3") (pin "A9") (pinfunction "NC_A9") (pintype "passive"))
    )
    (net (code "93") (name "unconnected-(D3R-NC-PadA10)") (class "Default")
      (node (ref "D3") (pin "A10") (pinfunction "NC_A10") (pintype "passive"))
    )
    (net (code "94") (name "unconnected-(D3R-NC-PadA25)") (class "Default")
      (node (ref "D3") (pin "A25") (pinfunction "NC_A25") (pintype "passive"))
    )
    (net (code "95") (name "unconnected-(D3R-NC-PadA27)") (class "Default")
      (node (ref "D3") (pin "A27") (pinfunction "NC_A27") (pintype "passive"))
    )
    (net (code "96") (name "unconnected-(D3R-NC-PadA28)") (class "Default")
      (node (ref "D3") (pin "A28") (pinfunction "NC_A28") (pintype "passive"))
    )
    (net (code "97") (name "unconnected-(D3R-NC-PadA29)") (class "Default")
      (node (ref "D3") (pin "A29") (pinfunction "NC_A29") (pintype "passive"))
    )
    (net (code "98") (name "unconnected-(D3R-NC-PadA30)") (class "Default")
      (node (ref "D3") (pin "A30") (pinfunction "NC_A30") (pintype "passive"))
    )
    (net (code "99") (name "unconnected-(D3R-NC-PadA32)") (class "Default")
      (node (ref "D3") (pin "A32") (pinfunction "NC_A32") (pintype "passive"))
    )
    (net (code "100") (name "unconnected-(D3R-NC-PadA33)") (class "Default")
      (node (ref "D3") (pin "A33") (pinfunction "NC_A33") (pintype "passive"))
    )
    (net (code "101") (name "unconnected-(D3R-NC-PadA34)") (class "Default")
      (node (ref "D3") (pin "A34") (pinfunction "NC_A34") (pintype "passive"))
    )
    (net (code "102") (name "unconnected-(D3R-NC-PadB1)") (class "Default")
      (node (ref "D3") (pin "B1") (pinfunction "NC_B1") (pintype "passive"))
    )
    (net (code "103") (name "unconnected-(D3R-NC-PadB2)") (class "Default")
      (node (ref "D3") (pin "B2") (pinfunction "NC_B2") (pintype "passive"))
    )
    (net (code "104") (name "unconnected-(D3R-NC-PadB4)") (class "Default")
      (node (ref "D3") (pin "B4") (pinfunction "NC_B4") (pintype "passive"))
    )
    (net (code "105") (name "unconnected-(D3R-NC-PadB5)") (class "Default")
      (node (ref "D3") (pin "B5") (pinfunction "NC_B5") (pintype "passive"))
    )
    (net (code "106") (name "unconnected-(D3R-NC-PadB6)") (class "Default")
      (node (ref "D3") (pin "B6") (pinfunction "NC_B6") (pintype "passive"))
    )
    (net (code "107") (name "unconnected-(D3R-NC-PadB7)") (class "Default")
      (node (ref "D3") (pin "B7") (pinfunction "NC_B7") (pintype "passive"))
    )
    (net (code "108") (name "unconnected-(D3R-NC-PadB9)") (class "Default")
      (node (ref "D3") (pin "B9") (pinfunction "NC_B9") (pintype "passive"))
    )
    (net (code "109") (name "unconnected-(D3R-NC-PadB10)") (class "Default")
      (node (ref "D3") (pin "B10") (pinfunction "NC_B10") (pintype "passive"))
    )
    (net (code "110") (name "unconnected-(D3R-NC-PadB11)") (class "Default")
      (node (ref "D3") (pin "B11") (pinfunction "NC_B11") (pintype "passive"))
    )
    (net (code "111") (name "unconnected-(D3R-NC-PadB25)") (class "Default")
      (node (ref "D3") (pin "B25") (pinfunction "NC_B25") (pintype "passive"))
    )
    (net (code "112") (name "unconnected-(D3R-NC-PadB26)") (class "Default")
      (node (ref "D3") (pin "B26") (pinfunction "NC_B26") (pintype "passive"))
    )
    (net (code "113") (name "unconnected-(D3R-NC-PadB27)") (class "Default")
      (node (ref "D3") (pin "B27") (pinfunction "NC_B27") (pintype "passive"))
    )
    (net (code "114") (name "unconnected-(D3R-NC-PadB29)") (class "Default")
      (node (ref "D3") (pin "B29") (pinfunction "NC_B29") (pintype "passive"))
    )
    (net (code "115") (name "unconnected-(D3R-NC-PadB30)") (class "Default")
      (node (ref "D3") (pin "B30") (pinfunction "NC_B30") (pintype "passive"))
    )
    (net (code "116") (name "unconnected-(D3R-NC-PadB31)") (class "Default")
      (node (ref "D3") (pin "B31") (pinfunction "NC_B31") (pintype "passive"))
    )
    (net (code "117") (name "unconnected-(D3R-NC-PadB32)") (class "Default")
      (node (ref "D3") (pin "B32") (pinfunction "NC_B32") (pintype "passive"))
    )
    (net (code "118") (name "unconnected-(D3R-NC-PadB34)") (class "Default")
      (node (ref "D3") (pin "B34") (pinfunction "NC_B34") (pintype "passive"))
    )
    (net (code "119") (name "unconnected-(D3R-NC-PadC1)") (class "Default")
      (node (ref "D3") (pin "C1") (pinfunction "NC_C1") (pintype "passive"))
    )
    (net (code "120") (name "unconnected-(D3R-NC-PadC2)") (class "Default")
      (node (ref "D3") (pin "C2") (pinfunction "NC_C2") (pintype "passive"))
    )
    (net (code "121") (name "unconnected-(D3R-NC-PadC3)") (class "Default")
      (node (ref "D3") (pin "C3") (pinfunction "NC_C3") (pintype "passive"))
    )
    (net (code "122") (name "unconnected-(D3R-NC-PadC4)") (class "Default")
      (node (ref "D3") (pin "C4") (pinfunction "NC_C4") (pintype "passive"))
    )
    (net (code "123") (name "unconnected-(D3R-NC-PadC6)") (class "Default")
      (node (ref "D3") (pin "C6") (pinfunction "NC_C6") (pintype "passive"))
    )
    (net (code "124") (name "unconnected-(D3R-NC-PadC7)") (class "Default")
      (node (ref "D3") (pin "C7") (pinfunction "NC_C7") (pintype "passive"))
    )
    (net (code "125") (name "unconnected-(D3R-NC-PadC8)") (class "Default")
      (node (ref "D3") (pin "C8") (pinfunction "NC_C8") (pintype "passive"))
    )
    (net (code "126") (name "unconnected-(D3R-NC-PadC9)") (class "Default")
      (node (ref "D3") (pin "C9") (pinfunction "NC_C9") (pintype "passive"))
    )
    (net (code "127") (name "unconnected-(D3R-NC-PadC11)") (class "Default")
      (node (ref "D3") (pin "C11") (pinfunction "NC_C11") (pintype "passive"))
    )
    (net (code "128") (name "unconnected-(D3R-NC-PadC26)") (class "Default")
      (node (ref "D3") (pin "C26") (pinfunction "NC_C26") (pintype "passive"))
    )
    (net (code "129") (name "unconnected-(D3R-NC-PadC27)") (class "Default")
      (node (ref "D3") (pin "C27") (pinfunction "NC_C27") (pintype "passive"))
    )
    (net (code "130") (name "unconnected-(D3R-NC-PadC28)") (class "Default")
      (node (ref "D3") (pin "C28") (pinfunction "NC_C28") (pintype "passive"))
    )
    (net (code "131") (name "unconnected-(D3R-NC-PadC29)") (class "Default")
      (node (ref "D3") (pin "C29") (pinfunction "NC_C29") (pintype "passive"))
    )
    (net (code "132") (name "unconnected-(D3R-NC-PadC31)") (class "Default")
      (node (ref "D3") (pin "C31") (pinfunction "NC_C31") (pintype "passive"))
    )
    (net (code "133") (name "unconnected-(D3R-NC-PadC32)") (class "Default")
      (node (ref "D3") (pin "C32") (pinfunction "NC_C32") (pintype "passive"))
    )
    (net (code "134") (name "unconnected-(D3R-NC-PadC33)") (class "Default")
      (node (ref "D3") (pin "C33") (pinfunction "NC_C33") (pintype "passive"))
    )
    (net (code "135") (name "unconnected-(D3R-NC-PadC34)") (class "Default")
      (node (ref "D3") (pin "C34") (pinfunction "NC_C34") (pintype "passive"))
    )
    (net (code "136") (name "unconnected-(D3R-NC-PadD1)") (class "Default")
      (node (ref "D3") (pin "D1") (pinfunction "NC_D1") (pintype "passive"))
    )
    (net (code "137") (name "unconnected-(D3R-NC-PadD3)") (class "Default")
      (node (ref "D3") (pin "D3") (pinfunction "NC_D3") (pintype "passive"))
    )
    (net (code "138") (name "unconnected-(D3R-NC-PadD4)") (class "Default")
      (node (ref "D3") (pin "D4") (pinfunction "NC_D4") (pintype "passive"))
    )
    (net (code "139") (name "unconnected-(D3R-NC-PadD5)") (class "Default")
      (node (ref "D3") (pin "D5") (pinfunction "NC_D5") (pintype "passive"))
    )
    (net (code "140") (name "unconnected-(D3R-NC-PadD6)") (class "Default")
      (node (ref "D3") (pin "D6") (pinfunction "NC_D6") (pintype "passive"))
    )
    (net (code "141") (name "unconnected-(D3R-NC-PadD8)") (class "Default")
      (node (ref "D3") (pin "D8") (pinfunction "NC_D8") (pintype "passive"))
    )
    (net (code "142") (name "unconnected-(D3R-NC-PadD9)") (class "Default")
      (node (ref "D3") (pin "D9") (pinfunction "NC_D9") (pintype "passive"))
    )
    (net (code "143") (name "unconnected-(D3R-NC-PadD10)") (class "Default")
      (node (ref "D3") (pin "D10") (pinfunction "NC_D10") (pintype "passive"))
    )
    (net (code "144") (name "unconnected-(D3R-NC-PadD11)") (class "Default")
      (node (ref "D3") (pin "D11") (pinfunction "NC_D11") (pintype "passive"))
    )
    (net (code "145") (name "unconnected-(D3R-NC-PadD24)") (class "Default")
      (node (ref "D3") (pin "D24") (pinfunction "NC_D24") (pintype "passive"))
    )
    (net (code "146") (name "unconnected-(D3R-NC-PadD25)") (class "Default")
      (node (ref "D3") (pin "D25") (pinfunction "NC_D25") (pintype "passive"))
    )
    (net (code "147") (name "unconnected-(D3R-NC-PadD26)") (class "Default")
      (node (ref "D3") (pin "D26") (pinfunction "NC_D26") (pintype "passive"))
    )
    (net (code "148") (name "unconnected-(D3R-NC-PadD28)") (class "Default")
      (node (ref "D3") (pin "D28") (pinfunction "NC_D28") (pintype "passive"))
    )
    (net (code "149") (name "unconnected-(D3R-NC-PadD29)") (class "Default")
      (node (ref "D3") (pin "D29") (pinfunction "NC_D29") (pintype "passive"))
    )
    (net (code "150") (name "unconnected-(D3R-NC-PadD30)") (class "Default")
      (node (ref "D3") (pin "D30") (pinfunction "NC_D30") (pintype "passive"))
    )
    (net (code "151") (name "unconnected-(D3R-NC-PadD31)") (class "Default")
      (node (ref "D3") (pin "D31") (pinfunction "NC_D31") (pintype "passive"))
    )
    (net (code "152") (name "unconnected-(D3R-NC-PadD33)") (class "Default")
      (node (ref "D3") (pin "D33") (pinfunction "NC_D33") (pintype "passive"))
    )
    (net (code "153") (name "unconnected-(D3R-NC-PadD34)") (class "Default")
      (node (ref "D3") (pin "D34") (pinfunction "NC_D34") (pintype "passive"))
    )
    (net (code "154") (name "unconnected-(D3R-NC-PadE1)") (class "Default")
      (node (ref "D3") (pin "E1") (pinfunction "NC_E1") (pintype "passive"))
    )
    (net (code "155") (name "unconnected-(D3R-NC-PadE2)") (class "Default")
      (node (ref "D3") (pin "E2") (pinfunction "NC_E2") (pintype "passive"))
    )
    (net (code "156") (name "unconnected-(D3R-NC-PadE3)") (class "Default")
      (node (ref "D3") (pin "E3") (pinfunction "NC_E3") (pintype "passive"))
    )
    (net (code "157") (name "unconnected-(D3R-NC-PadE5)") (class "Default")
      (node (ref "D3") (pin "E5") (pinfunction "NC_E5") (pintype "passive"))
    )
    (net (code "158") (name "unconnected-(D3R-NC-PadE6)") (class "Default")
      (node (ref "D3") (pin "E6") (pinfunction "NC_E6") (pintype "passive"))
    )
    (net (code "159") (name "unconnected-(D3R-NC-PadE7)") (class "Default")
      (node (ref "D3") (pin "E7") (pinfunction "NC_E7") (pintype "passive"))
    )
    (net (code "160") (name "unconnected-(D3R-NC-PadE8)") (class "Default")
      (node (ref "D3") (pin "E8") (pinfunction "NC_E8") (pintype "passive"))
    )
    (net (code "161") (name "unconnected-(D3R-NC-PadE10)") (class "Default")
      (node (ref "D3") (pin "E10") (pinfunction "NC_E10") (pintype "passive"))
    )
    (net (code "162") (name "unconnected-(D3R-NC-PadE11)") (class "Default")
      (node (ref "D3") (pin "E11") (pinfunction "NC_E11") (pintype "passive"))
    )
    (net (code "163") (name "unconnected-(D3R-NC-PadE25)") (class "Default")
      (node (ref "D3") (pin "E25") (pinfunction "NC_E25") (pintype "passive"))
    )
    (net (code "164") (name "unconnected-(D3R-NC-PadE26)") (class "Default")
      (node (ref "D3") (pin "E26") (pinfunction "NC_E26") (pintype "passive"))
    )
    (net (code "165") (name "unconnected-(D3R-NC-PadE27)") (class "Default")
      (node (ref "D3") (pin "E27") (pinfunction "NC_E27") (pintype "passive"))
    )
    (net (code "166") (name "unconnected-(D3R-NC-PadE28)") (class "Default")
      (node (ref "D3") (pin "E28") (pinfunction "NC_E28") (pintype "passive"))
    )
    (net (code "167") (name "unconnected-(D3R-NC-PadE30)") (class "Default")
      (node (ref "D3") (pin "E30") (pinfunction "NC_E30") (pintype "passive"))
    )
    (net (code "168") (name "unconnected-(D3R-NC-PadE31)") (class "Default")
      (node (ref "D3") (pin "E31") (pinfunction "NC_E31") (pintype "passive"))
    )
    (net (code "169") (name "unconnected-(D3R-NC-PadE32)") (class "Default")
      (node (ref "D3") (pin "E32") (pinfunction "NC_E32") (pintype "passive"))
    )
    (net (code "170") (name "unconnected-(D3R-NC-PadE33)") (class "Default")
      (node (ref "D3") (pin "E33") (pinfunction "NC_E33") (pintype "passive"))
    )
    (net (code "171") (name "unconnected-(D3R-NC-PadF4)") (class "Default")
      (node (ref "D3") (pin "F4") (pinfunction "NC_F4") (pintype "passive"))
    )
    (net (code "172") (name "unconnected-(D3R-NC-PadF5)") (class "Default")
      (node (ref "D3") (pin "F5") (pinfunction "NC_F5") (pintype "passive"))
    )
    (net (code "173") (name "unconnected-(D3R-NC-PadF7)") (class "Default")
      (node (ref "D3") (pin "F7") (pinfunction "NC_F7") (pintype "passive"))
    )
    (net (code "174") (name "unconnected-(D3R-NC-PadF8)") (class "Default")
      (node (ref "D3") (pin "F8") (pinfunction "NC_F8") (pintype "passive"))
    )
    (net (code "175") (name "unconnected-(D3R-NC-PadF9)") (class "Default")
      (node (ref "D3") (pin "F9") (pinfunction "NC_F9") (pintype "passive"))
    )
    (net (code "176") (name "unconnected-(D3R-NC-PadF10)") (class "Default")
      (node (ref "D3") (pin "F10") (pinfunction "NC_F10") (pintype "passive"))
    )
    (net (code "177") (name "unconnected-(D3R-NC-PadF24)") (class "Default")
      (node (ref "D3") (pin "F24") (pinfunction "NC_F24") (pintype "passive"))
    )
    (net (code "178") (name "unconnected-(D3R-NC-PadF25)") (class "Default")
      (node (ref "D3") (pin "F25") (pinfunction "NC_F25") (pintype "passive"))
    )
    (net (code "179") (name "unconnected-(D3R-NC-PadF27)") (class "Default")
      (node (ref "D3") (pin "F27") (pinfunction "NC_F27") (pintype "passive"))
    )
    (net (code "180") (name "unconnected-(D3R-NC-PadF28)") (class "Default")
      (node (ref "D3") (pin "F28") (pinfunction "NC_F28") (pintype "passive"))
    )
    (net (code "181") (name "unconnected-(D3R-NC-PadF29)") (class "Default")
      (node (ref "D3") (pin "F29") (pinfunction "NC_F29") (pintype "passive"))
    )
    (net (code "182") (name "unconnected-(D3R-NC-PadF30)") (class "Default")
      (node (ref "D3") (pin "F30") (pinfunction "NC_F30") (pintype "passive"))
    )
    (net (code "183") (name "unconnected-(D3R-NC-PadF32)") (class "Default")
      (node (ref "D3") (pin "F32") (pinfunction "NC_F32") (pintype "passive"))
    )
    (net (code "184") (name "unconnected-(D3R-NC-PadF33)") (class "Default")
      (node (ref "D3") (pin "F33") (pinfunction "NC_F33") (pintype "passive"))
    )
    (net (code "185") (name "unconnected-(D3R-NC-PadF34)") (class "Default")
      (node (ref "D3") (pin "F34") (pinfunction "NC_F34") (pintype "passive"))
    )
  )
)
